# Acorn_AudioHybrid.net
KiCad netlist of a schematic drawn in Altium Designer
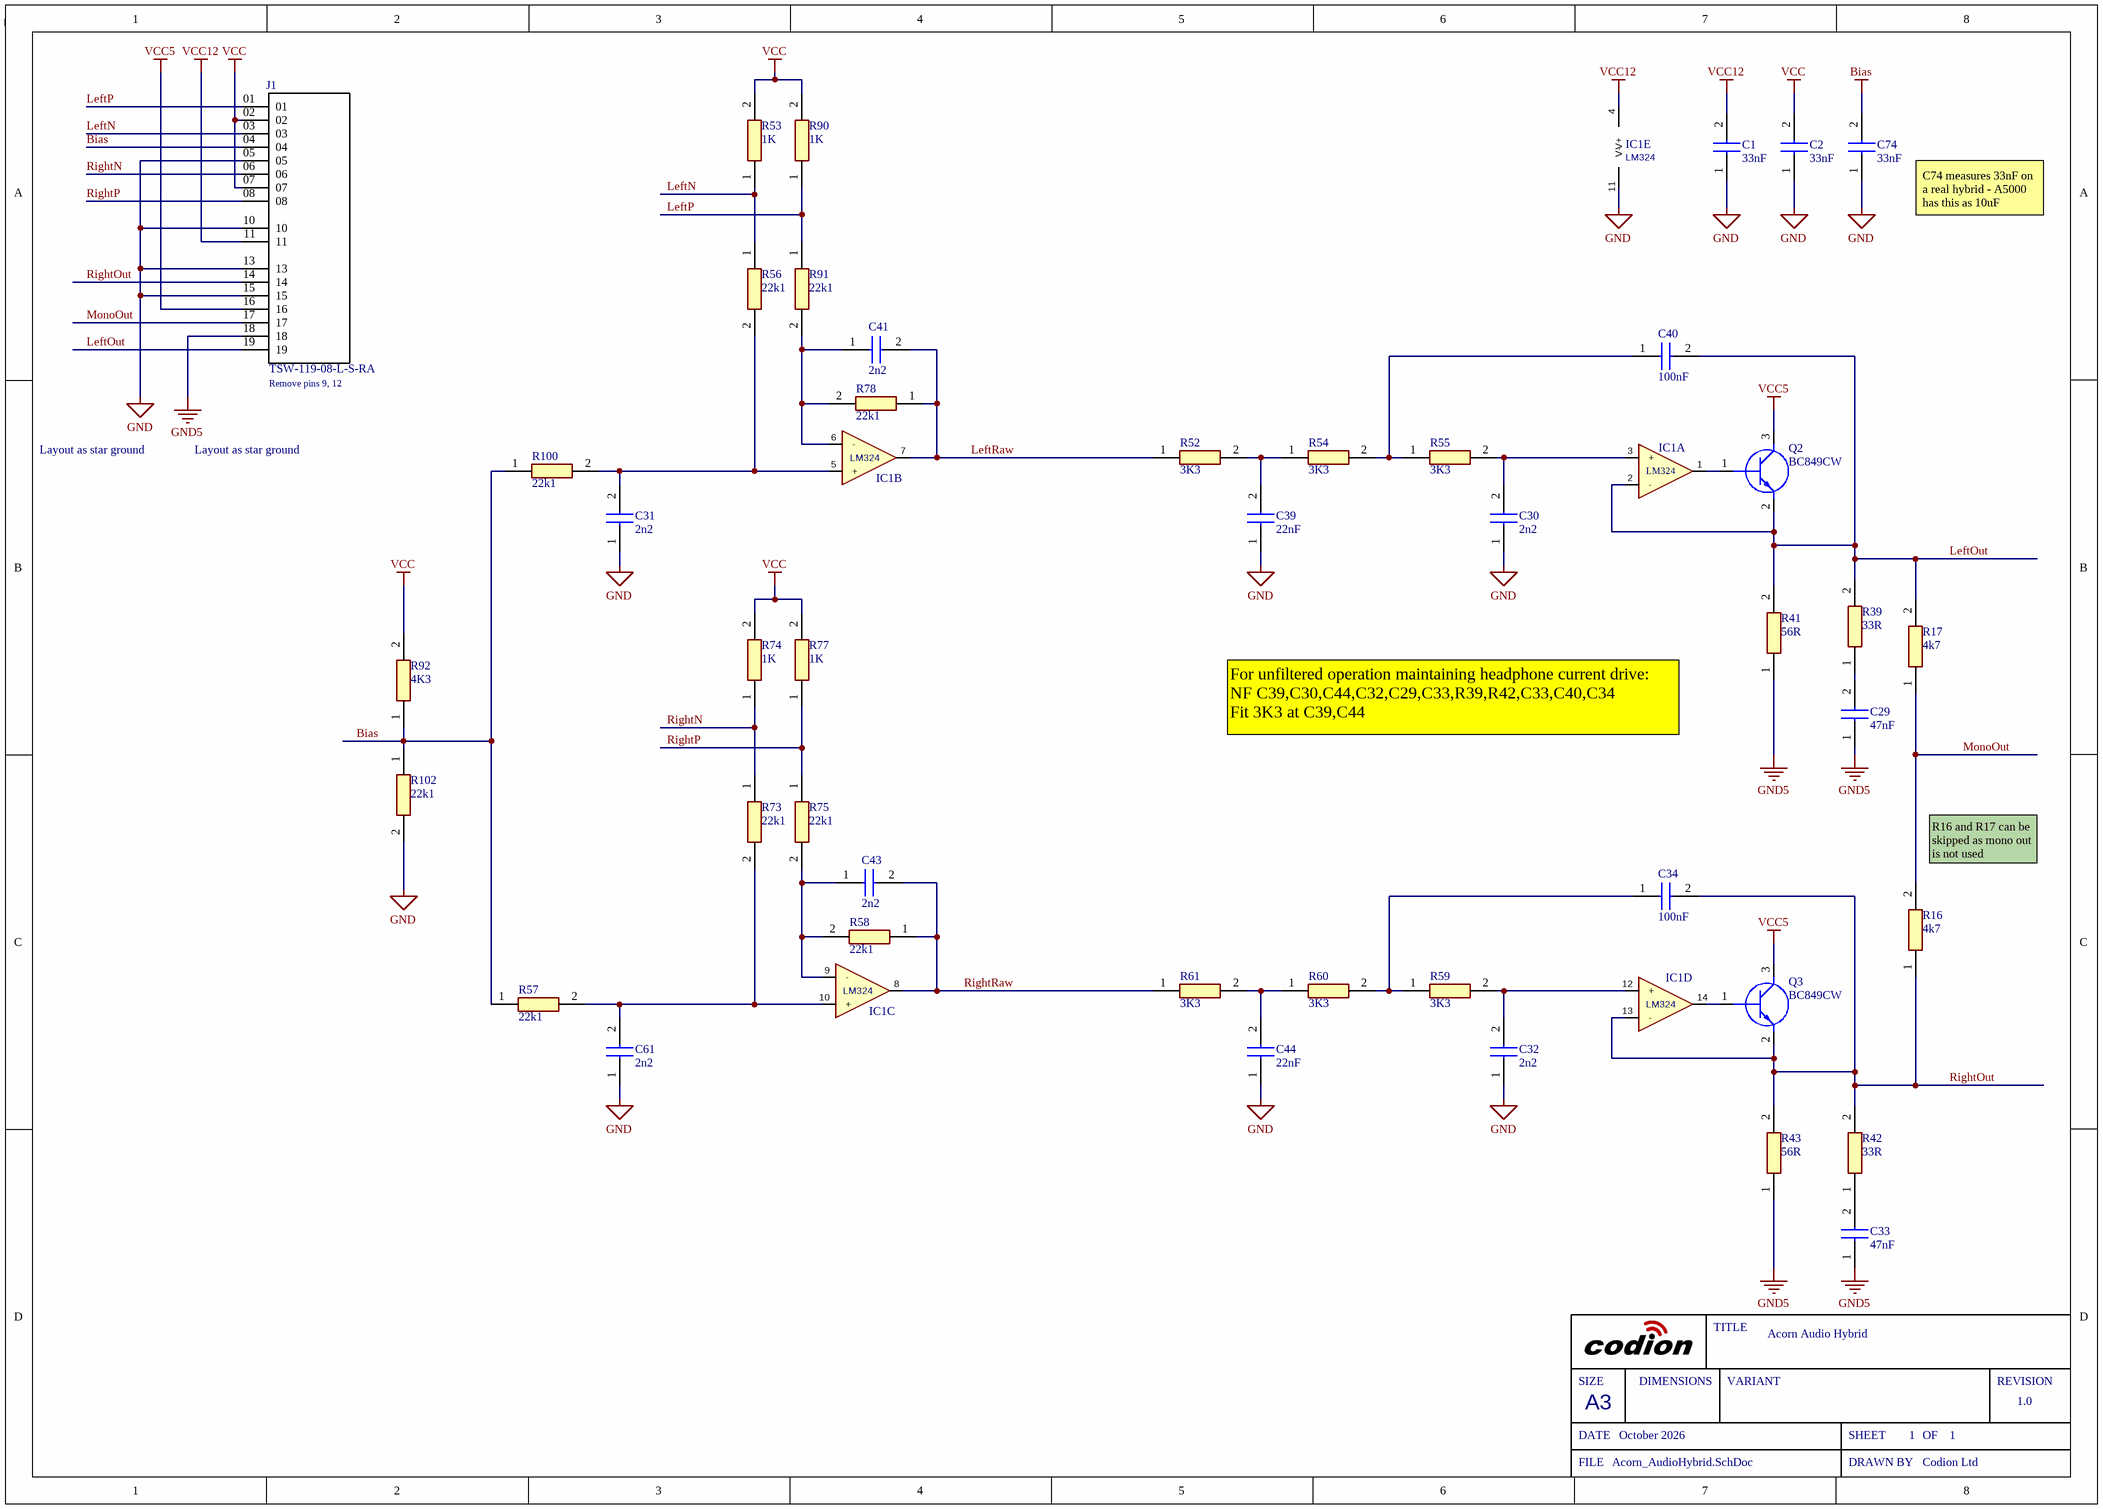
[diagram p0: Acorn_AudioHybrid.SchDoc]

(export (version "E")
  (design (tool "Eeschema 10.0.6"))
  (components
    (comp (ref "C1")
      (value "33nF")
      (footprint "SamacSys:CAPC2012X145N")
      (description "Capacitor")
      (fields
        (field (name "MANUFACTURER_PART_NUMBER") "C2012C0G1H333J125AA")
        (field (name "MOUSER PART NUMBER") "810-C2012C0G1H333J")
      )
      (libsource (lib "*") (part "C2012C0G1H333J125AA"))
    )
    (comp (ref "C2")
      (value "33nF")
      (footprint "SamacSys:CAPC2012X145N")
      (description "Capacitor")
      (fields
        (field (name "MANUFACTURER_PART_NUMBER") "C2012C0G1H333J125AA")
        (field (name "MOUSER PART NUMBER") "810-C2012C0G1H333J")
      )
      (libsource (lib "*") (part "C2012C0G1H333J125AA"))
    )
    (comp (ref "C29")
      (value "47nF")
      (footprint "SamacSys:C0402C104J4RACTU")
      (description "Capacitor")
      (fields
        (field (name "MANUFACTURER_PART_NUMBER") "C0402C473K3RECTU")
        (field (name "MOUSER PART NUMBER") "80-C0402C473K3RECTU")
      )
      (libsource (lib "*") (part "C0402C473K3RECTU"))
    )
    (comp (ref "C30")
      (value "2n2")
      (footprint "SamacSys:CAPC1005X55N")
      (description "Capacitor")
      (fields
        (field (name "MANUFACTURER_PART_NUMBER") "CGA2B3X7R1H223K050BB")
        (field (name "MOUSER PART NUMBER") "810-CGA2B3X7R1H223K")
      )
      (libsource (lib "*") (part "CGA2B3X7R1H223K050BB"))
    )
    (comp (ref "C31")
      (value "2n2")
      (footprint "SamacSys:CAPC1005X55N")
      (description "Capacitor")
      (fields
        (field (name "MANUFACTURER_PART_NUMBER") "CGA2B3X7R1H223K050BB")
        (field (name "MOUSER PART NUMBER") "810-CGA2B3X7R1H223K")
      )
      (libsource (lib "*") (part "CGA2B3X7R1H223K050BB"))
    )
    (comp (ref "C32")
      (value "2n2")
      (footprint "SamacSys:CAPC1005X55N")
      (description "Capacitor")
      (fields
        (field (name "MANUFACTURER_PART_NUMBER") "CGA2B3X7R1H223K050BB")
        (field (name "MOUSER PART NUMBER") "810-CGA2B3X7R1H223K")
      )
      (libsource (lib "*") (part "CGA2B3X7R1H223K050BB"))
    )
    (comp (ref "C33")
      (value "47nF")
      (footprint "SamacSys:C0402C104J4RACTU")
      (description "Capacitor")
      (fields
        (field (name "MANUFACTURER_PART_NUMBER") "C0402C473K3RECTU")
        (field (name "MOUSER PART NUMBER") "80-C0402C473K3RECTU")
      )
      (libsource (lib "*") (part "C0402C473K3RECTU"))
    )
    (comp (ref "C34")
      (value "100nF")
      (footprint "SamacSys:CAPC1005X55N")
      (description "Capacitor")
      (fields
        (field (name "MANUFACTURER_PART_NUMBER") "CL05B104KP5VPNC")
        (field (name "MOUSER PART NUMBER") "187-CL05B104KP5VPNC")
      )
      (libsource (lib "*") (part "CL05B104KP5VPNC"))
    )
    (comp (ref "C39")
      (value "22nF")
      (footprint "SamacSys:C0402")
      (description "Capacitor")
      (fields
        (field (name "MANUFACTURER_PART_NUMBER") "C0402C223K5REC7411")
        (field (name "MOUSER PART NUMBER") "80-C0402C223K5RECLR")
      )
      (libsource (lib "*") (part "C0402C223K5REC7411"))
    )
    (comp (ref "C40")
      (value "100nF")
      (footprint "SamacSys:CAPC1005X55N")
      (description "Capacitor")
      (fields
        (field (name "MANUFACTURER_PART_NUMBER") "CL05B104KP5VPNC")
        (field (name "MOUSER PART NUMBER") "187-CL05B104KP5VPNC")
      )
      (libsource (lib "*") (part "CL05B104KP5VPNC"))
    )
    (comp (ref "C41")
      (value "2n2")
      (footprint "SamacSys:CAPC1005X55N")
      (description "Capacitor")
      (fields
        (field (name "MANUFACTURER_PART_NUMBER") "CGA2B3X7R1H223K050BB")
        (field (name "MOUSER PART NUMBER") "810-CGA2B3X7R1H223K")
      )
      (libsource (lib "*") (part "CGA2B3X7R1H223K050BB"))
    )
    (comp (ref "C43")
      (value "2n2")
      (footprint "SamacSys:CAPC1005X55N")
      (description "Capacitor")
      (fields
        (field (name "MANUFACTURER_PART_NUMBER") "CGA2B3X7R1H223K050BB")
        (field (name "MOUSER PART NUMBER") "810-CGA2B3X7R1H223K")
      )
      (libsource (lib "*") (part "CGA2B3X7R1H223K050BB"))
    )
    (comp (ref "C44")
      (value "22nF")
      (footprint "SamacSys:C0402")
      (description "Capacitor")
      (fields
        (field (name "MANUFACTURER_PART_NUMBER") "C0402C223K5REC7411")
        (field (name "MOUSER PART NUMBER") "80-C0402C223K5RECLR")
      )
      (libsource (lib "*") (part "C0402C223K5REC7411"))
    )
    (comp (ref "C61")
      (value "2n2")
      (footprint "SamacSys:CAPC1005X55N")
      (description "Capacitor")
      (fields
        (field (name "MANUFACTURER_PART_NUMBER") "CGA2B3X7R1H223K050BB")
        (field (name "MOUSER PART NUMBER") "810-CGA2B3X7R1H223K")
      )
      (libsource (lib "*") (part "CGA2B3X7R1H223K050BB"))
    )
    (comp (ref "C74")
      (value "33nF")
      (footprint "SamacSys:CAPC2012X145N")
      (description "Capacitor")
      (fields
        (field (name "MANUFACTURER_PART_NUMBER") "C2012C0G1H333J125AA")
        (field (name "MOUSER PART NUMBER") "810-C2012C0G1H333J")
      )
      (libsource (lib "*") (part "C2012C0G1H333J125AA"))
    )
    (comp (ref "IC1")
      (value "LM324")
      (footprint "SOIC127P600X180-14N")
      (fields (field (name "Comment") "LM324M"))
      (libsource (lib "Amplifier_Operational") (part "LM324"))
    )
    (comp (ref "J1")
      (value "TSW-119-08-L-S-RA")
      (footprint "*SAMTEC_TSW-119-08-L-S-RA_TSW-119-08-L-S-RA(Primary)")
      (description "None")
      (fields (field (name "MF") "Samtec Inc."))
      (libsource (lib "TSW-119-08-L-S-RA") (part "TSW-119-08-L-S-RA"))
    )
    (comp (ref "Q2")
      (value "BC849CW")
      (footprint "SamacSys:SOT65P210X110-3N")
      (description "Transistor BJT NPN")
      (libsource (lib "*") (part "BC849CW"))
    )
    (comp (ref "Q3")
      (value "BC849CW")
      (footprint "SamacSys:SOT65P210X110-3N")
      (description "Transistor BJT NPN")
      (libsource (lib "*") (part "BC849CW"))
    )
    (comp (ref "R16")
      (value "4k7")
      (footprint "SamacSys:RESC1005X40N")
      (description "Resistor")
      (fields
        (field (name "MANUFACTURER_PART_NUMBER") "CRCW04024K70FKED")
        (field (name "MOUSER PART NUMBER") "71-CRCW0402-4.7K-E3")
      )
      (libsource (lib "*") (part "CRCW04024K70FKED"))
    )
    (comp (ref "R17")
      (value "4k7")
      (footprint "SamacSys:RESC1005X40N")
      (description "Resistor")
      (fields
        (field (name "MANUFACTURER_PART_NUMBER") "CRCW04024K70FKED")
        (field (name "MOUSER PART NUMBER") "71-CRCW0402-4.7K-E3")
      )
      (libsource (lib "*") (part "CRCW04024K70FKED"))
    )
    (comp (ref "R39")
      (value "33R")
      (footprint "SamacSys:RESC1005X40N")
      (description "Resistor")
      (fields
        (field (name "MANUFACTURER_PART_NUMBER") "CRCW040233R0FKED")
        (field (name "MOUSER PART NUMBER") "71-CRCW0402-33-E3")
      )
      (libsource (lib "SamacSys") (part "CRCW040233R0FKED"))
    )
    (comp (ref "R41")
      (value "56R")
      (footprint "SamacSys:CRCW0402200KFKED")
      (description "Resistor")
      (fields
        (field (name "MANUFACTURER_PART_NUMBER") "CRCW040256R2FKED")
        (field (name "MOUSER PART NUMBER") "71-CRCW0402-56.2-E3")
      )
      (libsource (lib "*") (part "CRCW040256R2FKED"))
    )
    (comp (ref "R42")
      (value "33R")
      (footprint "SamacSys:RESC1005X40N")
      (description "Resistor")
      (fields
        (field (name "MANUFACTURER_PART_NUMBER") "CRCW040233R0FKED")
        (field (name "MOUSER PART NUMBER") "71-CRCW0402-33-E3")
      )
      (libsource (lib "SamacSys") (part "CRCW040233R0FKED"))
    )
    (comp (ref "R43")
      (value "56R")
      (footprint "SamacSys:CRCW0402200KFKED")
      (description "Resistor")
      (fields
        (field (name "MANUFACTURER_PART_NUMBER") "CRCW040256R2FKED")
        (field (name "MOUSER PART NUMBER") "71-CRCW0402-56.2-E3")
      )
      (libsource (lib "*") (part "CRCW040256R2FKED"))
    )
    (comp (ref "R52")
      (value "3K3")
      (footprint "SamacSys:CRCW0402200KFKED")
      (description "Resistor")
      (fields
        (field (name "MANUFACTURER_PART_NUMBER") "CRCW04023K30FKED")
        (field (name "MOUSER PART NUMBER") "71-CRCW0402-3.3K-E3")
      )
      (libsource (lib "*") (part "CRCW04023K30FKED"))
    )
    (comp (ref "R53")
      (value "1K")
      (footprint "SamacSys:RESC1005X40N")
      (description "Resistor")
      (fields
        (field (name "MANUFACTURER_PART_NUMBER") "RC0402FR-7W1KL")
        (field (name "MOUSER PART NUMBER") "603-RC0402FR-7W1KL")
      )
      (libsource (lib "*") (part "RC0402FR-7W1KL"))
    )
    (comp (ref "R54")
      (value "3K3")
      (footprint "SamacSys:CRCW0402200KFKED")
      (description "Resistor")
      (fields
        (field (name "MANUFACTURER_PART_NUMBER") "CRCW04023K30FKED")
        (field (name "MOUSER PART NUMBER") "71-CRCW0402-3.3K-E3")
      )
      (libsource (lib "*") (part "CRCW04023K30FKED"))
    )
    (comp (ref "R55")
      (value "3K3")
      (footprint "SamacSys:CRCW0402200KFKED")
      (description "Resistor")
      (fields
        (field (name "MANUFACTURER_PART_NUMBER") "CRCW04023K30FKED")
        (field (name "MOUSER PART NUMBER") "71-CRCW0402-3.3K-E3")
      )
      (libsource (lib "*") (part "CRCW04023K30FKED"))
    )
    (comp (ref "R56")
      (value "22k1")
      (footprint "SamacSys:RESC1005X40N")
      (description "Resistor")
      (fields
        (field (name "MANUFACTURER_PART_NUMBER") "CRCW040222K1FKED")
        (field (name "MOUSER PART NUMBER") "71-CRCW0402-22.1K-E3")
      )
      (libsource (lib "") (part "CRCW040222K1FKED_1"))
    )
    (comp (ref "R57")
      (value "22k1")
      (footprint "SamacSys:RESC1005X40N")
      (description "Resistor")
      (fields
        (field (name "MANUFACTURER_PART_NUMBER") "CRCW040222K1FKED")
        (field (name "MOUSER PART NUMBER") "71-CRCW0402-22.1K-E3")
      )
      (libsource (lib "") (part "CRCW040222K1FKED_2"))
    )
    (comp (ref "R58")
      (value "22k1")
      (footprint "SamacSys:RESC1005X40N")
      (description "Resistor")
      (fields
        (field (name "MANUFACTURER_PART_NUMBER") "CRCW040222K1FKED")
        (field (name "MOUSER PART NUMBER") "71-CRCW0402-22.1K-E3")
      )
      (libsource (lib "*") (part "CRCW040222K1FKED"))
    )
    (comp (ref "R59")
      (value "3K3")
      (footprint "SamacSys:CRCW0402200KFKED")
      (description "Resistor")
      (fields
        (field (name "MANUFACTURER_PART_NUMBER") "CRCW04023K30FKED")
        (field (name "MOUSER PART NUMBER") "71-CRCW0402-3.3K-E3")
      )
      (libsource (lib "*") (part "CRCW04023K30FKED"))
    )
    (comp (ref "R60")
      (value "3K3")
      (footprint "SamacSys:CRCW0402200KFKED")
      (description "Resistor")
      (fields
        (field (name "MANUFACTURER_PART_NUMBER") "CRCW04023K30FKED")
        (field (name "MOUSER PART NUMBER") "71-CRCW0402-3.3K-E3")
      )
      (libsource (lib "*") (part "CRCW04023K30FKED"))
    )
    (comp (ref "R61")
      (value "3K3")
      (footprint "SamacSys:CRCW0402200KFKED")
      (description "Resistor")
      (fields
        (field (name "MANUFACTURER_PART_NUMBER") "CRCW04023K30FKED")
        (field (name "MOUSER PART NUMBER") "71-CRCW0402-3.3K-E3")
      )
      (libsource (lib "*") (part "CRCW04023K30FKED"))
    )
    (comp (ref "R73")
      (value "22k1")
      (footprint "SamacSys:RESC1005X40N")
      (description "Resistor")
      (fields
        (field (name "MANUFACTURER_PART_NUMBER") "CRCW040222K1FKED")
        (field (name "MOUSER PART NUMBER") "71-CRCW0402-22.1K-E3")
      )
      (libsource (lib "") (part "CRCW040222K1FKED_1"))
    )
    (comp (ref "R74")
      (value "1K")
      (footprint "SamacSys:RESC1005X40N")
      (description "Resistor")
      (fields
        (field (name "MANUFACTURER_PART_NUMBER") "RC0402FR-7W1KL")
        (field (name "MOUSER PART NUMBER") "603-RC0402FR-7W1KL")
      )
      (libsource (lib "*") (part "RC0402FR-7W1KL"))
    )
    (comp (ref "R75")
      (value "22k1")
      (footprint "SamacSys:RESC1005X40N")
      (description "Resistor")
      (fields
        (field (name "MANUFACTURER_PART_NUMBER") "CRCW040222K1FKED")
        (field (name "MOUSER PART NUMBER") "71-CRCW0402-22.1K-E3")
      )
      (libsource (lib "") (part "CRCW040222K1FKED_1"))
    )
    (comp (ref "R77")
      (value "1K")
      (footprint "SamacSys:RESC1005X40N")
      (description "Resistor")
      (fields
        (field (name "MANUFACTURER_PART_NUMBER") "RC0402FR-7W1KL")
        (field (name "MOUSER PART NUMBER") "603-RC0402FR-7W1KL")
      )
      (libsource (lib "*") (part "RC0402FR-7W1KL"))
    )
    (comp (ref "R78")
      (value "22k1")
      (footprint "SamacSys:RESC1005X40N")
      (description "Resistor")
      (fields
        (field (name "MANUFACTURER_PART_NUMBER") "CRCW040222K1FKED")
        (field (name "MOUSER PART NUMBER") "71-CRCW0402-22.1K-E3")
      )
      (libsource (lib "*") (part "CRCW040222K1FKED"))
    )
    (comp (ref "R90")
      (value "1K")
      (footprint "SamacSys:RESC1005X40N")
      (description "Resistor")
      (fields
        (field (name "MANUFACTURER_PART_NUMBER") "RC0402FR-7W1KL")
        (field (name "MOUSER PART NUMBER") "603-RC0402FR-7W1KL")
      )
      (libsource (lib "*") (part "RC0402FR-7W1KL"))
    )
    (comp (ref "R91")
      (value "22k1")
      (footprint "SamacSys:RESC1005X40N")
      (description "Resistor")
      (fields
        (field (name "MANUFACTURER_PART_NUMBER") "CRCW040222K1FKED")
        (field (name "MOUSER PART NUMBER") "71-CRCW0402-22.1K-E3")
      )
      (libsource (lib "") (part "CRCW040222K1FKED_1"))
    )
    (comp (ref "R92")
      (value "4K3")
      (footprint "SamacSys:RESC1005X40N")
      (description "Resistor")
      (fields
        (field (name "MANUFACTURER_PART_NUMBER") "RC0402FR-0710KP")
        (field (name "MOUSER PART NUMBER") "603-RC0402FR-0710KP")
      )
      (libsource (lib "*") (part "RC0402FR-0710KP"))
    )
    (comp (ref "R100")
      (value "22k1")
      (footprint "SamacSys:RESC1005X40N")
      (description "Resistor")
      (fields
        (field (name "MANUFACTURER_PART_NUMBER") "CRCW040222K1FKED")
        (field (name "MOUSER PART NUMBER") "71-CRCW0402-22.1K-E3")
      )
      (libsource (lib "") (part "CRCW040222K1FKED_2"))
    )
    (comp (ref "R102")
      (value "22k1")
      (footprint "SamacSys:RESC1005X40N")
      (description "Resistor")
      (fields
        (field (name "MANUFACTURER_PART_NUMBER") "CRCW04024K70FKED")
        (field (name "MOUSER PART NUMBER") "71-CRCW0402-4.7K-E3")
      )
      (libsource (lib "") (part "CRCW04024K70FKED_1"))
    )
  )
  (nets
    (net (code "1") (name "/LeftN") (class "Default")
      (node (ref "J1") (pin "03") (pinfunction "03_03") (pintype "passive"))
      (node (ref "R53") (pin "1") (pinfunction "1_1") (pintype "passive"))
      (node (ref "R56") (pin "1") (pinfunction "1_1") (pintype "passive"))
    )
    (net (code "2") (name "/LeftOut") (class "Default")
      (node (ref "C40") (pin "2") (pinfunction "2_2") (pintype "passive"))
      (node (ref "IC1") (pin "2") (pinfunction "-_2") (pintype "passive"))
      (node (ref "J1") (pin "19") (pinfunction "19_19") (pintype "passive"))
      (node (ref "Q2") (pin "2") (pinfunction "E_2") (pintype "passive"))
      (node (ref "R17") (pin "2") (pinfunction "2_2") (pintype "passive"))
      (node (ref "R39") (pin "2") (pinfunction "2_2") (pintype "passive"))
      (node (ref "R41") (pin "2") (pinfunction "2_2") (pintype "passive"))
    )
    (net (code "3") (name "/LeftP") (class "Default")
      (node (ref "J1") (pin "01") (pinfunction "01_01") (pintype "passive"))
      (node (ref "R90") (pin "1") (pinfunction "1_1") (pintype "passive"))
      (node (ref "R91") (pin "1") (pinfunction "1_1") (pintype "passive"))
    )
    (net (code "4") (name "/LeftRaw") (class "Default")
      (node (ref "C41") (pin "2") (pinfunction "2_2") (pintype "passive"))
      (node (ref "IC1") (pin "7") (pinfunction "7_7") (pintype "passive"))
      (node (ref "R52") (pin "1") (pinfunction "1_1") (pintype "passive"))
      (node (ref "R78") (pin "1") (pinfunction "1_1") (pintype "passive"))
    )
    (net (code "5") (name "/MonoOut") (class "Default")
      (node (ref "J1") (pin "17") (pinfunction "17_17") (pintype "passive"))
      (node (ref "R16") (pin "2") (pinfunction "2_2") (pintype "passive"))
      (node (ref "R17") (pin "1") (pinfunction "1_1") (pintype "passive"))
    )
    (net (code "6") (name "/RightN") (class "Default")
      (node (ref "J1") (pin "06") (pinfunction "06_06") (pintype "passive"))
      (node (ref "R73") (pin "1") (pinfunction "1_1") (pintype "passive"))
      (node (ref "R74") (pin "1") (pinfunction "1_1") (pintype "passive"))
    )
    (net (code "7") (name "/RightOut") (class "Default")
      (node (ref "C34") (pin "2") (pinfunction "2_2") (pintype "passive"))
      (node (ref "IC1") (pin "13") (pinfunction "-_13") (pintype "passive"))
      (node (ref "J1") (pin "14") (pinfunction "14_14") (pintype "passive"))
      (node (ref "Q3") (pin "2") (pinfunction "E_2") (pintype "passive"))
      (node (ref "R16") (pin "1") (pinfunction "1_1") (pintype "passive"))
      (node (ref "R42") (pin "2") (pinfunction "2_2") (pintype "passive"))
      (node (ref "R43") (pin "2") (pinfunction "2_2") (pintype "passive"))
    )
    (net (code "8") (name "/RightP") (class "Default")
      (node (ref "J1") (pin "08") (pinfunction "08_08") (pintype "passive"))
      (node (ref "R75") (pin "1") (pinfunction "1_1") (pintype "passive"))
      (node (ref "R77") (pin "1") (pinfunction "1_1") (pintype "passive"))
    )
    (net (code "9") (name "/RightRaw") (class "Default")
      (node (ref "C43") (pin "2") (pinfunction "2_2") (pintype "passive"))
      (node (ref "IC1") (pin "8") (pinfunction "8_8") (pintype "passive"))
      (node (ref "R58") (pin "1") (pinfunction "1_1") (pintype "passive"))
      (node (ref "R61") (pin "1") (pinfunction "1_1") (pintype "passive"))
    )
    (net (code "10") (name "Bias") (class "Default")
      (node (ref "C74") (pin "2") (pinfunction "2_2") (pintype "passive"))
      (node (ref "J1") (pin "04") (pinfunction "04_04") (pintype "passive"))
      (node (ref "R100") (pin "1") (pinfunction "1_1") (pintype "passive"))
      (node (ref "R102") (pin "1") (pinfunction "1_1") (pintype "passive"))
      (node (ref "R57") (pin "1") (pinfunction "1_1") (pintype "passive"))
      (node (ref "R92") (pin "1") (pinfunction "1_1") (pintype "passive"))
    )
    (net (code "11") (name "GND") (class "Default")
      (node (ref "C1") (pin "1") (pinfunction "1_1") (pintype "passive"))
      (node (ref "C2") (pin "1") (pinfunction "1_1") (pintype "passive"))
      (node (ref "C30") (pin "1") (pinfunction "1_1") (pintype "passive"))
      (node (ref "C31") (pin "1") (pinfunction "1_1") (pintype "passive"))
      (node (ref "C32") (pin "1") (pinfunction "1_1") (pintype "passive"))
      (node (ref "C39") (pin "1") (pinfunction "1_1") (pintype "passive"))
      (node (ref "C44") (pin "1") (pinfunction "1_1") (pintype "passive"))
      (node (ref "C61") (pin "1") (pinfunction "1_1") (pintype "passive"))
      (node (ref "C74") (pin "1") (pinfunction "1_1") (pintype "passive"))
      (node (ref "IC1") (pin "11") (pinfunction "V-_11") (pintype "passive"))
      (node (ref "J1") (pin "05") (pinfunction "05_05") (pintype "passive"))
      (node (ref "J1") (pin "10") (pinfunction "10_10") (pintype "passive"))
      (node (ref "J1") (pin "13") (pinfunction "13_13") (pintype "passive"))
      (node (ref "J1") (pin "15") (pinfunction "15_15") (pintype "passive"))
      (node (ref "R102") (pin "2") (pinfunction "2_2") (pintype "passive"))
    )
    (net (code "12") (name "GND5") (class "Default")
      (node (ref "C29") (pin "1") (pinfunction "1_1") (pintype "passive"))
      (node (ref "C33") (pin "1") (pinfunction "1_1") (pintype "passive"))
      (node (ref "J1") (pin "18") (pinfunction "18_18") (pintype "passive"))
      (node (ref "R41") (pin "1") (pinfunction "1_1") (pintype "passive"))
      (node (ref "R43") (pin "1") (pinfunction "1_1") (pintype "passive"))
    )
    (net (code "13") (name "Net-(C29-Pad2)") (class "Default")
      (node (ref "C29") (pin "2") (pinfunction "2_2") (pintype "passive"))
      (node (ref "R39") (pin "1") (pinfunction "1_1") (pintype "passive"))
    )
    (net (code "14") (name "Net-(C33-Pad2)") (class "Default")
      (node (ref "C33") (pin "2") (pinfunction "2_2") (pintype "passive"))
      (node (ref "R42") (pin "1") (pinfunction "1_1") (pintype "passive"))
    )
    (net (code "15") (name "Net-(C34-Pad1)") (class "Default")
      (node (ref "C34") (pin "1") (pinfunction "1_1") (pintype "passive"))
      (node (ref "R59") (pin "1") (pinfunction "1_1") (pintype "passive"))
      (node (ref "R60") (pin "2") (pinfunction "2_2") (pintype "passive"))
    )
    (net (code "16") (name "Net-(C39-Pad2)") (class "Default")
      (node (ref "C39") (pin "2") (pinfunction "2_2") (pintype "passive"))
      (node (ref "R52") (pin "2") (pinfunction "2_2") (pintype "passive"))
      (node (ref "R54") (pin "1") (pinfunction "1_1") (pintype "passive"))
    )
    (net (code "17") (name "Net-(C40-Pad1)") (class "Default")
      (node (ref "C40") (pin "1") (pinfunction "1_1") (pintype "passive"))
      (node (ref "R54") (pin "2") (pinfunction "2_2") (pintype "passive"))
      (node (ref "R55") (pin "1") (pinfunction "1_1") (pintype "passive"))
    )
    (net (code "18") (name "Net-(C44-Pad2)") (class "Default")
      (node (ref "C44") (pin "2") (pinfunction "2_2") (pintype "passive"))
      (node (ref "R60") (pin "1") (pinfunction "1_1") (pintype "passive"))
      (node (ref "R61") (pin "2") (pinfunction "2_2") (pintype "passive"))
    )
    (net (code "19") (name "Net-(IC1A-+)") (class "Default")
      (node (ref "C30") (pin "2") (pinfunction "2_2") (pintype "passive"))
      (node (ref "IC1") (pin "3") (pinfunction "+_3") (pintype "passive"))
      (node (ref "R55") (pin "2") (pinfunction "2_2") (pintype "passive"))
    )
    (net (code "20") (name "Net-(IC1B-+)") (class "Default")
      (node (ref "C31") (pin "2") (pinfunction "2_2") (pintype "passive"))
      (node (ref "IC1") (pin "5") (pinfunction "+_5") (pintype "passive"))
      (node (ref "R100") (pin "2") (pinfunction "2_2") (pintype "passive"))
      (node (ref "R56") (pin "2") (pinfunction "2_2") (pintype "passive"))
    )
    (net (code "21") (name "Net-(IC1B--)") (class "Default")
      (node (ref "C41") (pin "1") (pinfunction "1_1") (pintype "passive"))
      (node (ref "IC1") (pin "6") (pinfunction "-_6") (pintype "passive"))
      (node (ref "R78") (pin "2") (pinfunction "2_2") (pintype "passive"))
      (node (ref "R91") (pin "2") (pinfunction "2_2") (pintype "passive"))
    )
    (net (code "22") (name "Net-(IC1C-+)") (class "Default")
      (node (ref "C61") (pin "2") (pinfunction "2_2") (pintype "passive"))
      (node (ref "IC1") (pin "10") (pinfunction "+_10") (pintype "passive"))
      (node (ref "R57") (pin "2") (pinfunction "2_2") (pintype "passive"))
      (node (ref "R73") (pin "2") (pinfunction "2_2") (pintype "passive"))
    )
    (net (code "23") (name "Net-(IC1C--)") (class "Default")
      (node (ref "C43") (pin "1") (pinfunction "1_1") (pintype "passive"))
      (node (ref "IC1") (pin "9") (pinfunction "-_9") (pintype "passive"))
      (node (ref "R58") (pin "2") (pinfunction "2_2") (pintype "passive"))
      (node (ref "R75") (pin "2") (pinfunction "2_2") (pintype "passive"))
    )
    (net (code "24") (name "Net-(IC1D-+)") (class "Default")
      (node (ref "C32") (pin "2") (pinfunction "2_2") (pintype "passive"))
      (node (ref "IC1") (pin "12") (pinfunction "+_12") (pintype "passive"))
      (node (ref "R59") (pin "2") (pinfunction "2_2") (pintype "passive"))
    )
    (net (code "25") (name "Net-(Q2-B)") (class "Default")
      (node (ref "IC1") (pin "1") (pinfunction "1_1") (pintype "passive"))
      (node (ref "Q2") (pin "1") (pinfunction "B_1") (pintype "passive"))
    )
    (net (code "26") (name "Net-(Q3-B)") (class "Default")
      (node (ref "IC1") (pin "14") (pinfunction "14_14") (pintype "passive"))
      (node (ref "Q3") (pin "1") (pinfunction "B_1") (pintype "passive"))
    )
    (net (code "27") (name "VCC") (class "Default")
      (node (ref "C2") (pin "2") (pinfunction "2_2") (pintype "passive"))
      (node (ref "J1") (pin "02") (pinfunction "02_02") (pintype "passive"))
      (node (ref "J1") (pin "07") (pinfunction "07_07") (pintype "passive"))
      (node (ref "R53") (pin "2") (pinfunction "2_2") (pintype "passive"))
      (node (ref "R74") (pin "2") (pinfunction "2_2") (pintype "passive"))
      (node (ref "R77") (pin "2") (pinfunction "2_2") (pintype "passive"))
      (node (ref "R90") (pin "2") (pinfunction "2_2") (pintype "passive"))
      (node (ref "R92") (pin "2") (pinfunction "2_2") (pintype "passive"))
    )
    (net (code "28") (name "VCC5") (class "Default")
      (node (ref "J1") (pin "16") (pinfunction "16_16") (pintype "passive"))
      (node (ref "Q2") (pin "3") (pinfunction "C_3") (pintype "passive"))
      (node (ref "Q3") (pin "3") (pinfunction "C_3") (pintype "passive"))
    )
    (net (code "29") (name "VCC12") (class "Default")
      (node (ref "C1") (pin "2") (pinfunction "2_2") (pintype "passive"))
      (node (ref "IC1") (pin "4") (pinfunction "V+_4") (pintype "passive"))
      (node (ref "J1") (pin "11") (pinfunction "11_11") (pintype "passive"))
    )
  )
)
